# headphone.net
KiCad netlist of a schematic drawn in EAGLE
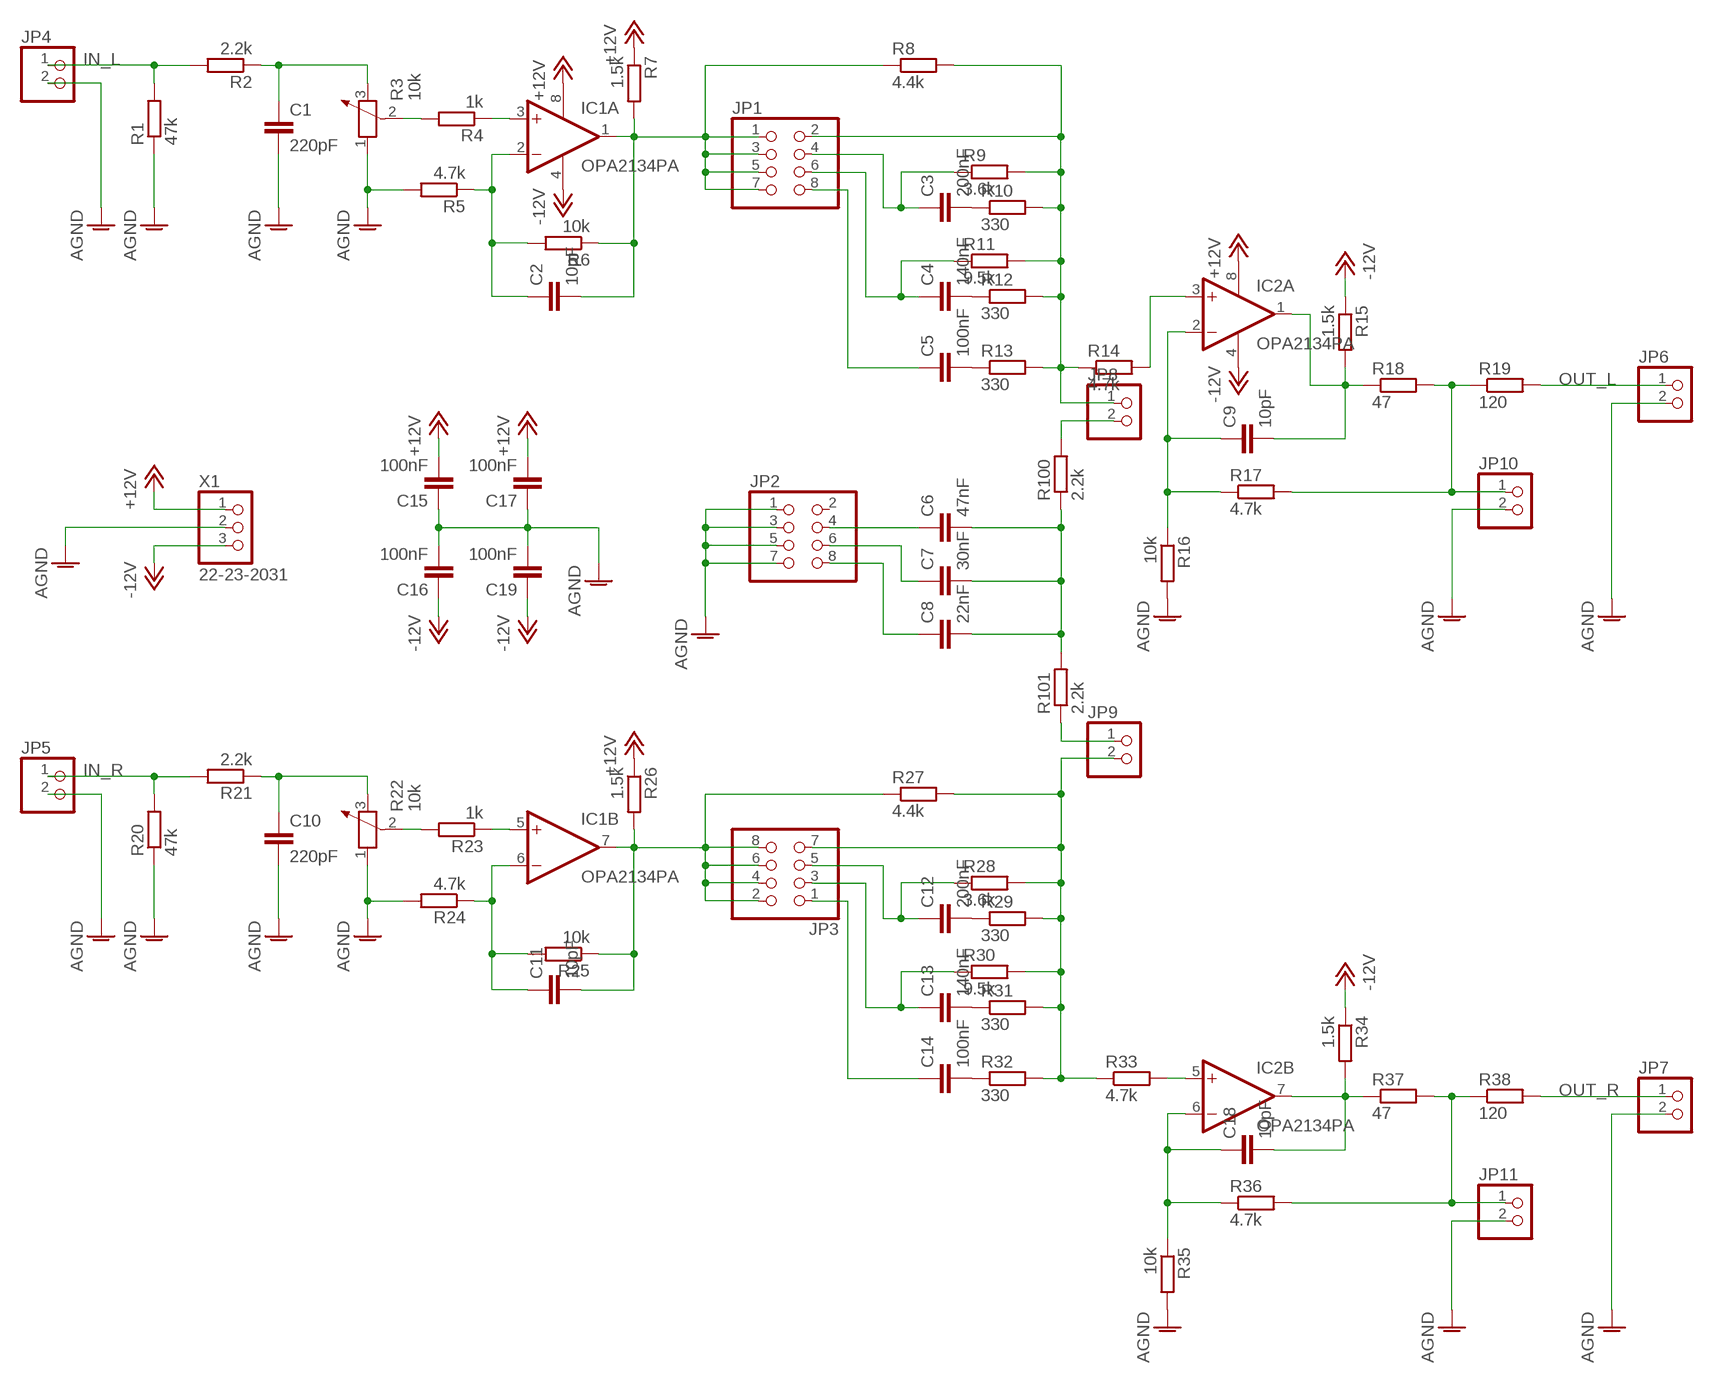
[diagram p0: schematic, sheet 1]

(export (version "E")
  (design (tool "Eeschema 10.0.6"))
  (components
    (comp (ref "C1")
      (value "220pF")
      (footprint "eagle-import:C025-025X050")
      (libsource (lib "eagle-import") (part "C-EU025-025X050"))
    )
    (comp (ref "C2")
      (value "10pF")
      (footprint "eagle-import:C050-025X075")
      (libsource (lib "eagle-import") (part "C-EU050-025X075"))
    )
    (comp (ref "C3")
      (value "200nF")
      (footprint "eagle-import:C050-025X075")
      (libsource (lib "eagle-import") (part "C-EU050-025X075"))
    )
    (comp (ref "C4")
      (value "140nF")
      (footprint "eagle-import:C050-025X075")
      (libsource (lib "eagle-import") (part "C-EU050-025X075"))
    )
    (comp (ref "C5")
      (value "100nF")
      (footprint "eagle-import:C050-025X075")
      (libsource (lib "eagle-import") (part "C-EU050-025X075"))
    )
    (comp (ref "C6")
      (value "47nF")
      (footprint "eagle-import:C050-025X075")
      (libsource (lib "eagle-import") (part "C-EU050-025X075"))
    )
    (comp (ref "C7")
      (value "30nF")
      (footprint "eagle-import:C050-025X075")
      (libsource (lib "eagle-import") (part "C-EU050-025X075"))
    )
    (comp (ref "C8")
      (value "22nF")
      (footprint "eagle-import:C050-025X075")
      (libsource (lib "eagle-import") (part "C-EU050-025X075"))
    )
    (comp (ref "C9")
      (value "10pF")
      (footprint "eagle-import:C050-025X075")
      (libsource (lib "eagle-import") (part "C-EU050-025X075"))
    )
    (comp (ref "C10")
      (value "220pF")
      (footprint "eagle-import:C025-025X050")
      (libsource (lib "eagle-import") (part "C-EU025-025X050"))
    )
    (comp (ref "C11")
      (value "10pF")
      (footprint "eagle-import:C050-025X075")
      (libsource (lib "eagle-import") (part "C-EU050-025X075"))
    )
    (comp (ref "C12")
      (value "200nF")
      (footprint "eagle-import:C050-025X075")
      (libsource (lib "eagle-import") (part "C-EU050-025X075"))
    )
    (comp (ref "C13")
      (value "140nF")
      (footprint "eagle-import:C050-025X075")
      (libsource (lib "eagle-import") (part "C-EU050-025X075"))
    )
    (comp (ref "C14")
      (value "100nF")
      (footprint "eagle-import:C050-025X075")
      (libsource (lib "eagle-import") (part "C-EU050-025X075"))
    )
    (comp (ref "C15")
      (value "100nF")
      (footprint "eagle-import:C050-025X075")
      (libsource (lib "eagle-import") (part "C-EU050-025X075"))
    )
    (comp (ref "C16")
      (value "100nF")
      (footprint "eagle-import:C050-025X075")
      (libsource (lib "eagle-import") (part "C-EU050-025X075"))
    )
    (comp (ref "C17")
      (value "100nF")
      (footprint "eagle-import:C050-025X075")
      (libsource (lib "eagle-import") (part "C-EU050-025X075"))
    )
    (comp (ref "C18")
      (value "10pF")
      (footprint "eagle-import:C050-025X075")
      (libsource (lib "eagle-import") (part "C-EU050-025X075"))
    )
    (comp (ref "C19")
      (value "100nF")
      (footprint "eagle-import:C050-025X075")
      (libsource (lib "eagle-import") (part "C-EU050-025X075"))
    )
    (comp (ref "IC1")
      (value "OPA2134PA")
      (footprint "eagle-import:DIL08")
      (libsource (lib "eagle-import") (part "OPA2PA134"))
    )
    (comp (ref "IC2")
      (value "OPA2134PA")
      (footprint "eagle-import:DIL08")
      (libsource (lib "eagle-import") (part "OPA2PA134"))
    )
    (comp (ref "JP1")
      (value "PINHD-2X4")
      (footprint "eagle-import:2X04")
      (libsource (lib "eagle-import") (part "PINHD-2X4"))
    )
    (comp (ref "JP2")
      (value "PINHD-2X4")
      (footprint "eagle-import:2X04")
      (libsource (lib "eagle-import") (part "PINHD-2X4"))
    )
    (comp (ref "JP3")
      (value "PINHD-2X4")
      (footprint "eagle-import:2X04")
      (libsource (lib "eagle-import") (part "PINHD-2X4"))
    )
    (comp (ref "JP4")
      (value "PINHD-1X2")
      (footprint "eagle-import:1X02")
      (libsource (lib "eagle-import") (part "PINHD-1X2"))
    )
    (comp (ref "JP5")
      (value "PINHD-1X2")
      (footprint "eagle-import:1X02")
      (libsource (lib "eagle-import") (part "PINHD-1X2"))
    )
    (comp (ref "JP6")
      (value "PINHD-1X2")
      (footprint "eagle-import:1X02")
      (libsource (lib "eagle-import") (part "PINHD-1X2"))
    )
    (comp (ref "JP7")
      (value "PINHD-1X2")
      (footprint "eagle-import:1X02")
      (libsource (lib "eagle-import") (part "PINHD-1X2"))
    )
    (comp (ref "JP8")
      (value "PINHD-1X2")
      (footprint "eagle-import:1X02")
      (libsource (lib "eagle-import") (part "PINHD-1X2"))
    )
    (comp (ref "JP9")
      (value "PINHD-1X2")
      (footprint "eagle-import:1X02")
      (libsource (lib "eagle-import") (part "PINHD-1X2"))
    )
    (comp (ref "JP10")
      (value "PINHD-1X2")
      (footprint "eagle-import:1X02")
      (libsource (lib "eagle-import") (part "PINHD-1X2"))
    )
    (comp (ref "JP11")
      (value "PINHD-1X2")
      (footprint "eagle-import:1X02")
      (libsource (lib "eagle-import") (part "PINHD-1X2"))
    )
    (comp (ref "R1")
      (value "47k")
      (footprint "eagle-import:0207_7")
      (libsource (lib "eagle-import") (part "R-EU_0207/7"))
    )
    (comp (ref "R2")
      (value "2.2k")
      (footprint "eagle-import:0207_7")
      (libsource (lib "eagle-import") (part "R-EU_0207/7"))
    )
    (comp (ref "R3")
      (value "10k")
      (footprint "eagle-import:1X03")
      (libsource (lib "eagle-import") (part "POTENTIOMETER_"))
    )
    (comp (ref "R4")
      (value "1k")
      (footprint "eagle-import:0207_7")
      (libsource (lib "eagle-import") (part "R-EU_0207/7"))
    )
    (comp (ref "R5")
      (value "4.7k")
      (footprint "eagle-import:0207_7")
      (libsource (lib "eagle-import") (part "R-EU_0207/7"))
    )
    (comp (ref "R6")
      (value "10k")
      (footprint "eagle-import:0207_7")
      (libsource (lib "eagle-import") (part "R-EU_0207/7"))
    )
    (comp (ref "R7")
      (value "1.5k")
      (footprint "eagle-import:0207_7")
      (libsource (lib "eagle-import") (part "R-EU_0207/7"))
    )
    (comp (ref "R8")
      (value "4.4k")
      (footprint "eagle-import:0207_7")
      (libsource (lib "eagle-import") (part "R-EU_0207/7"))
    )
    (comp (ref "R9")
      (value "3.6k")
      (footprint "eagle-import:0207_7")
      (libsource (lib "eagle-import") (part "R-EU_0207/7"))
    )
    (comp (ref "R10")
      (value "330")
      (footprint "eagle-import:0207_7")
      (libsource (lib "eagle-import") (part "R-EU_0207/7"))
    )
    (comp (ref "R11")
      (value "9.5k")
      (footprint "eagle-import:0207_7")
      (libsource (lib "eagle-import") (part "R-EU_0207/7"))
    )
    (comp (ref "R12")
      (value "330")
      (footprint "eagle-import:0207_7")
      (libsource (lib "eagle-import") (part "R-EU_0207/7"))
    )
    (comp (ref "R13")
      (value "330")
      (footprint "eagle-import:0207_7")
      (libsource (lib "eagle-import") (part "R-EU_0207/7"))
    )
    (comp (ref "R14")
      (value "4.7k")
      (footprint "eagle-import:0207_7")
      (libsource (lib "eagle-import") (part "R-EU_0207/7"))
    )
    (comp (ref "R15")
      (value "1.5k")
      (footprint "eagle-import:0207_7")
      (libsource (lib "eagle-import") (part "R-EU_0207/7"))
    )
    (comp (ref "R16")
      (value "10k")
      (footprint "eagle-import:0207_7")
      (libsource (lib "eagle-import") (part "R-EU_0207/7"))
    )
    (comp (ref "R17")
      (value "4.7k")
      (footprint "eagle-import:0207_7")
      (libsource (lib "eagle-import") (part "R-EU_0207/7"))
    )
    (comp (ref "R18")
      (value "47")
      (footprint "eagle-import:0207_7")
      (libsource (lib "eagle-import") (part "R-EU_0207/7"))
    )
    (comp (ref "R19")
      (value "120")
      (footprint "eagle-import:0207_7")
      (libsource (lib "eagle-import") (part "R-EU_0207/7"))
    )
    (comp (ref "R20")
      (value "47k")
      (footprint "eagle-import:0207_7")
      (libsource (lib "eagle-import") (part "R-EU_0207/7"))
    )
    (comp (ref "R21")
      (value "2.2k")
      (footprint "eagle-import:0207_7")
      (libsource (lib "eagle-import") (part "R-EU_0207/7"))
    )
    (comp (ref "R22")
      (value "10k")
      (footprint "eagle-import:1X03")
      (libsource (lib "eagle-import") (part "POTENTIOMETER_"))
    )
    (comp (ref "R23")
      (value "1k")
      (footprint "eagle-import:0207_7")
      (libsource (lib "eagle-import") (part "R-EU_0207/7"))
    )
    (comp (ref "R24")
      (value "4.7k")
      (footprint "eagle-import:0207_7")
      (libsource (lib "eagle-import") (part "R-EU_0207/7"))
    )
    (comp (ref "R25")
      (value "10k")
      (footprint "eagle-import:0207_7")
      (libsource (lib "eagle-import") (part "R-EU_0207/7"))
    )
    (comp (ref "R26")
      (value "1.5k")
      (footprint "eagle-import:0207_7")
      (libsource (lib "eagle-import") (part "R-EU_0207/7"))
    )
    (comp (ref "R27")
      (value "4.4k")
      (footprint "eagle-import:0207_7")
      (libsource (lib "eagle-import") (part "R-EU_0207/7"))
    )
    (comp (ref "R28")
      (value "3.6k")
      (footprint "eagle-import:0207_7")
      (libsource (lib "eagle-import") (part "R-EU_0207/7"))
    )
    (comp (ref "R29")
      (value "330")
      (footprint "eagle-import:0207_7")
      (libsource (lib "eagle-import") (part "R-EU_0207/7"))
    )
    (comp (ref "R30")
      (value "9.5k")
      (footprint "eagle-import:0207_7")
      (libsource (lib "eagle-import") (part "R-EU_0207/7"))
    )
    (comp (ref "R31")
      (value "330")
      (footprint "eagle-import:0207_7")
      (libsource (lib "eagle-import") (part "R-EU_0207/7"))
    )
    (comp (ref "R32")
      (value "330")
      (footprint "eagle-import:0207_7")
      (libsource (lib "eagle-import") (part "R-EU_0207/7"))
    )
    (comp (ref "R33")
      (value "4.7k")
      (footprint "eagle-import:0207_7")
      (libsource (lib "eagle-import") (part "R-EU_0207/7"))
    )
    (comp (ref "R34")
      (value "1.5k")
      (footprint "eagle-import:0207_7")
      (libsource (lib "eagle-import") (part "R-EU_0207/7"))
    )
    (comp (ref "R35")
      (value "10k")
      (footprint "eagle-import:0207_7")
      (libsource (lib "eagle-import") (part "R-EU_0207/7"))
    )
    (comp (ref "R36")
      (value "4.7k")
      (footprint "eagle-import:0207_7")
      (libsource (lib "eagle-import") (part "R-EU_0207/7"))
    )
    (comp (ref "R37")
      (value "47")
      (footprint "eagle-import:0207_7")
      (libsource (lib "eagle-import") (part "R-EU_0207/7"))
    )
    (comp (ref "R38")
      (value "120")
      (footprint "eagle-import:0207_7")
      (libsource (lib "eagle-import") (part "R-EU_0207/7"))
    )
    (comp (ref "R100")
      (value "2.2k")
      (footprint "eagle-import:0207_7")
      (libsource (lib "eagle-import") (part "R-EU_0207/7"))
    )
    (comp (ref "R101")
      (value "2.2k")
      (footprint "eagle-import:0207_7")
      (libsource (lib "eagle-import") (part "R-EU_0207/7"))
    )
    (comp (ref "X1")
      (value "22-23-2031")
      (footprint "eagle-import:22-23-2031")
      (libsource (lib "eagle-import") (part "22-23-2031"))
    )
  )
  (nets
    (net (code "1") (name "+12V") (class "Default")
      (node (ref "C15") (pin "2") (pinfunction "2_2") (pintype "passive"))
      (node (ref "C17") (pin "2") (pinfunction "2_2") (pintype "passive"))
      (node (ref "IC1") (pin "8") (pinfunction "V+_8") (pintype "power_in"))
      (node (ref "IC2") (pin "8") (pinfunction "V+_8") (pintype "power_in"))
      (node (ref "R26") (pin "1") (pinfunction "1_1") (pintype "passive"))
      (node (ref "R7") (pin "1") (pinfunction "1_1") (pintype "passive"))
      (node (ref "X1") (pin "1") (pinfunction "1_1") (pintype "passive"))
    )
    (net (code "2") (name "-12V") (class "Default")
      (node (ref "C16") (pin "1") (pinfunction "1_1") (pintype "passive"))
      (node (ref "C19") (pin "1") (pinfunction "1_1") (pintype "passive"))
      (node (ref "IC1") (pin "4") (pinfunction "V-_4") (pintype "power_in"))
      (node (ref "IC2") (pin "4") (pinfunction "V-_4") (pintype "power_in"))
      (node (ref "R15") (pin "1") (pinfunction "1_1") (pintype "passive"))
      (node (ref "R34") (pin "1") (pinfunction "1_1") (pintype "passive"))
      (node (ref "X1") (pin "3") (pinfunction "3_3") (pintype "passive"))
    )
    (net (code "3") (name "/IN_L") (class "Default")
      (node (ref "JP4") (pin "1") (pinfunction "1_1") (pintype "passive"))
      (node (ref "R1") (pin "2") (pinfunction "2_2") (pintype "passive"))
      (node (ref "R2") (pin "2") (pinfunction "2_2") (pintype "passive"))
    )
    (net (code "4") (name "/IN_R") (class "Default")
      (node (ref "JP5") (pin "1") (pinfunction "1_1") (pintype "passive"))
      (node (ref "R20") (pin "2") (pinfunction "2_2") (pintype "passive"))
      (node (ref "R21") (pin "2") (pinfunction "2_2") (pintype "passive"))
    )
    (net (code "5") (name "/OUT_L") (class "Default")
      (node (ref "JP6") (pin "1") (pinfunction "1_1") (pintype "passive"))
      (node (ref "R19") (pin "2") (pinfunction "2_2") (pintype "passive"))
    )
    (net (code "6") (name "/OUT_R") (class "Default")
      (node (ref "JP7") (pin "1") (pinfunction "1_1") (pintype "passive"))
      (node (ref "R38") (pin "2") (pinfunction "2_2") (pintype "passive"))
    )
    (net (code "7") (name "AGND") (class "Default")
      (node (ref "C1") (pin "2") (pinfunction "2_2") (pintype "passive"))
      (node (ref "C10") (pin "2") (pinfunction "2_2") (pintype "passive"))
      (node (ref "C15") (pin "1") (pinfunction "1_1") (pintype "passive"))
      (node (ref "C16") (pin "2") (pinfunction "2_2") (pintype "passive"))
      (node (ref "C17") (pin "1") (pinfunction "1_1") (pintype "passive"))
      (node (ref "C19") (pin "2") (pinfunction "2_2") (pintype "passive"))
      (node (ref "JP10") (pin "2") (pinfunction "2_2") (pintype "passive"))
      (node (ref "JP11") (pin "2") (pinfunction "2_2") (pintype "passive"))
      (node (ref "JP2") (pin "1") (pinfunction "1_1") (pintype "passive"))
      (node (ref "JP2") (pin "3") (pinfunction "3_3") (pintype "passive"))
      (node (ref "JP2") (pin "5") (pinfunction "5_5") (pintype "passive"))
      (node (ref "JP2") (pin "7") (pinfunction "7_7") (pintype "passive"))
      (node (ref "JP4") (pin "2") (pinfunction "2_2") (pintype "passive"))
      (node (ref "JP5") (pin "2") (pinfunction "2_2") (pintype "passive"))
      (node (ref "JP6") (pin "2") (pinfunction "2_2") (pintype "passive"))
      (node (ref "JP7") (pin "2") (pinfunction "2_2") (pintype "passive"))
      (node (ref "R1") (pin "1") (pinfunction "1_1") (pintype "passive"))
      (node (ref "R16") (pin "2") (pinfunction "2_2") (pintype "passive"))
      (node (ref "R20") (pin "1") (pinfunction "1_1") (pintype "passive"))
      (node (ref "R22") (pin "1") (pinfunction "1_1") (pintype "passive"))
      (node (ref "R24") (pin "2") (pinfunction "2_2") (pintype "passive"))
      (node (ref "R3") (pin "1") (pinfunction "1_1") (pintype "passive"))
      (node (ref "R35") (pin "2") (pinfunction "2_2") (pintype "passive"))
      (node (ref "R5") (pin "2") (pinfunction "2_2") (pintype "passive"))
      (node (ref "X1") (pin "2") (pinfunction "2_2") (pintype "passive"))
    )
    (net (code "8") (name "Net-(C3-Pad1)") (class "Default")
      (node (ref "C3") (pin "1") (pinfunction "1_1") (pintype "passive"))
      (node (ref "JP1") (pin "4") (pinfunction "4_4") (pintype "passive"))
      (node (ref "R9") (pin "1") (pinfunction "1_1") (pintype "passive"))
    )
    (net (code "9") (name "Net-(C3-Pad2)") (class "Default")
      (node (ref "C3") (pin "2") (pinfunction "2_2") (pintype "passive"))
      (node (ref "R10") (pin "1") (pinfunction "1_1") (pintype "passive"))
    )
    (net (code "10") (name "Net-(C4-Pad1)") (class "Default")
      (node (ref "C4") (pin "1") (pinfunction "1_1") (pintype "passive"))
      (node (ref "JP1") (pin "6") (pinfunction "6_6") (pintype "passive"))
      (node (ref "R11") (pin "1") (pinfunction "1_1") (pintype "passive"))
    )
    (net (code "11") (name "Net-(C4-Pad2)") (class "Default")
      (node (ref "C4") (pin "2") (pinfunction "2_2") (pintype "passive"))
      (node (ref "R12") (pin "1") (pinfunction "1_1") (pintype "passive"))
    )
    (net (code "12") (name "Net-(C5-Pad1)") (class "Default")
      (node (ref "C5") (pin "1") (pinfunction "1_1") (pintype "passive"))
      (node (ref "JP1") (pin "8") (pinfunction "8_8") (pintype "passive"))
    )
    (net (code "13") (name "Net-(C5-Pad2)") (class "Default")
      (node (ref "C5") (pin "2") (pinfunction "2_2") (pintype "passive"))
      (node (ref "R13") (pin "1") (pinfunction "1_1") (pintype "passive"))
    )
    (net (code "14") (name "Net-(C6-Pad1)") (class "Default")
      (node (ref "C6") (pin "1") (pinfunction "1_1") (pintype "passive"))
      (node (ref "JP2") (pin "4") (pinfunction "4_4") (pintype "passive"))
    )
    (net (code "15") (name "Net-(C6-Pad2)") (class "Default")
      (node (ref "C6") (pin "2") (pinfunction "2_2") (pintype "passive"))
      (node (ref "C7") (pin "2") (pinfunction "2_2") (pintype "passive"))
      (node (ref "C8") (pin "2") (pinfunction "2_2") (pintype "passive"))
      (node (ref "R100") (pin "1") (pinfunction "1_1") (pintype "passive"))
      (node (ref "R101") (pin "2") (pinfunction "2_2") (pintype "passive"))
    )
    (net (code "16") (name "Net-(C7-Pad1)") (class "Default")
      (node (ref "C7") (pin "1") (pinfunction "1_1") (pintype "passive"))
      (node (ref "JP2") (pin "6") (pinfunction "6_6") (pintype "passive"))
    )
    (net (code "17") (name "Net-(C8-Pad1)") (class "Default")
      (node (ref "C8") (pin "1") (pinfunction "1_1") (pintype "passive"))
      (node (ref "JP2") (pin "8") (pinfunction "8_8") (pintype "passive"))
    )
    (net (code "18") (name "Net-(C12-Pad1)") (class "Default")
      (node (ref "C12") (pin "1") (pinfunction "1_1") (pintype "passive"))
      (node (ref "JP3") (pin "5") (pinfunction "5_5") (pintype "passive"))
      (node (ref "R28") (pin "1") (pinfunction "1_1") (pintype "passive"))
    )
    (net (code "19") (name "Net-(C12-Pad2)") (class "Default")
      (node (ref "C12") (pin "2") (pinfunction "2_2") (pintype "passive"))
      (node (ref "R29") (pin "1") (pinfunction "1_1") (pintype "passive"))
    )
    (net (code "20") (name "Net-(C13-Pad1)") (class "Default")
      (node (ref "C13") (pin "1") (pinfunction "1_1") (pintype "passive"))
      (node (ref "JP3") (pin "3") (pinfunction "3_3") (pintype "passive"))
      (node (ref "R30") (pin "1") (pinfunction "1_1") (pintype "passive"))
    )
    (net (code "21") (name "Net-(C13-Pad2)") (class "Default")
      (node (ref "C13") (pin "2") (pinfunction "2_2") (pintype "passive"))
      (node (ref "R31") (pin "1") (pinfunction "1_1") (pintype "passive"))
    )
    (net (code "22") (name "Net-(C14-Pad1)") (class "Default")
      (node (ref "C14") (pin "1") (pinfunction "1_1") (pintype "passive"))
      (node (ref "JP3") (pin "1") (pinfunction "1_1") (pintype "passive"))
    )
    (net (code "23") (name "Net-(C14-Pad2)") (class "Default")
      (node (ref "C14") (pin "2") (pinfunction "2_2") (pintype "passive"))
      (node (ref "R32") (pin "1") (pinfunction "1_1") (pintype "passive"))
    )
    (net (code "24") (name "Net-(IC1A-+IN)") (class "Default")
      (node (ref "IC1") (pin "3") (pinfunction "+IN_3") (pintype "input"))
      (node (ref "R4") (pin "1") (pinfunction "1_1") (pintype "passive"))
    )
    (net (code "25") (name "Net-(IC1A--IN)") (class "Default")
      (node (ref "C2") (pin "1") (pinfunction "1_1") (pintype "passive"))
      (node (ref "IC1") (pin "2") (pinfunction "-IN_2") (pintype "input"))
      (node (ref "R5") (pin "1") (pinfunction "1_1") (pintype "passive"))
      (node (ref "R6") (pin "2") (pinfunction "2_2") (pintype "passive"))
    )
    (net (code "26") (name "Net-(IC1A-OUT)") (class "Default")
      (node (ref "C2") (pin "2") (pinfunction "2_2") (pintype "passive"))
      (node (ref "IC1") (pin "1") (pinfunction "OUT_1") (pintype "output"))
      (node (ref "JP1") (pin "1") (pinfunction "1_1") (pintype "passive"))
      (node (ref "JP1") (pin "3") (pinfunction "3_3") (pintype "passive"))
      (node (ref "JP1") (pin "5") (pinfunction "5_5") (pintype "passive"))
      (node (ref "JP1") (pin "7") (pinfunction "7_7") (pintype "passive"))
      (node (ref "R6") (pin "1") (pinfunction "1_1") (pintype "passive"))
      (node (ref "R7") (pin "2") (pinfunction "2_2") (pintype "passive"))
      (node (ref "R8") (pin "1") (pinfunction "1_1") (pintype "passive"))
    )
    (net (code "27") (name "Net-(IC1B-+IN)") (class "Default")
      (node (ref "IC1") (pin "5") (pinfunction "+IN_5") (pintype "input"))
      (node (ref "R23") (pin "1") (pinfunction "1_1") (pintype "passive"))
    )
    (net (code "28") (name "Net-(IC1B--IN)") (class "Default")
      (node (ref "C11") (pin "1") (pinfunction "1_1") (pintype "passive"))
      (node (ref "IC1") (pin "6") (pinfunction "-IN_6") (pintype "input"))
      (node (ref "R24") (pin "1") (pinfunction "1_1") (pintype "passive"))
      (node (ref "R25") (pin "2") (pinfunction "2_2") (pintype "passive"))
    )
    (net (code "29") (name "Net-(IC1B-OUT)") (class "Default")
      (node (ref "C11") (pin "2") (pinfunction "2_2") (pintype "passive"))
      (node (ref "IC1") (pin "7") (pinfunction "OUT_7") (pintype "output"))
      (node (ref "JP3") (pin "2") (pinfunction "2_2") (pintype "passive"))
      (node (ref "JP3") (pin "4") (pinfunction "4_4") (pintype "passive"))
      (node (ref "JP3") (pin "6") (pinfunction "6_6") (pintype "passive"))
      (node (ref "JP3") (pin "8") (pinfunction "8_8") (pintype "passive"))
      (node (ref "R25") (pin "1") (pinfunction "1_1") (pintype "passive"))
      (node (ref "R26") (pin "2") (pinfunction "2_2") (pintype "passive"))
      (node (ref "R27") (pin "1") (pinfunction "1_1") (pintype "passive"))
    )
    (net (code "30") (name "Net-(IC2A-+IN)") (class "Default")
      (node (ref "IC2") (pin "3") (pinfunction "+IN_3") (pintype "input"))
      (node (ref "R14") (pin "2") (pinfunction "2_2") (pintype "passive"))
    )
    (net (code "31") (name "Net-(IC2A--IN)") (class "Default")
      (node (ref "C9") (pin "1") (pinfunction "1_1") (pintype "passive"))
      (node (ref "IC2") (pin "2") (pinfunction "-IN_2") (pintype "input"))
      (node (ref "R16") (pin "1") (pinfunction "1_1") (pintype "passive"))
      (node (ref "R17") (pin "1") (pinfunction "1_1") (pintype "passive"))
    )
    (net (code "32") (name "Net-(IC2A-OUT)") (class "Default")
      (node (ref "C9") (pin "2") (pinfunction "2_2") (pintype "passive"))
      (node (ref "IC2") (pin "1") (pinfunction "OUT_1") (pintype "output"))
      (node (ref "R15") (pin "2") (pinfunction "2_2") (pintype "passive"))
      (node (ref "R18") (pin "1") (pinfunction "1_1") (pintype "passive"))
    )
    (net (code "33") (name "Net-(IC2B-+IN)") (class "Default")
      (node (ref "IC2") (pin "5") (pinfunction "+IN_5") (pintype "input"))
      (node (ref "R33") (pin "2") (pinfunction "2_2") (pintype "passive"))
    )
    (net (code "34") (name "Net-(IC2B--IN)") (class "Default")
      (node (ref "C18") (pin "1") (pinfunction "1_1") (pintype "passive"))
      (node (ref "IC2") (pin "6") (pinfunction "-IN_6") (pintype "input"))
      (node (ref "R35") (pin "1") (pinfunction "1_1") (pintype "passive"))
      (node (ref "R36") (pin "1") (pinfunction "1_1") (pintype "passive"))
    )
    (net (code "35") (name "Net-(IC2B-OUT)") (class "Default")
      (node (ref "C18") (pin "2") (pinfunction "2_2") (pintype "passive"))
      (node (ref "IC2") (pin "7") (pinfunction "OUT_7") (pintype "output"))
      (node (ref "R34") (pin "2") (pinfunction "2_2") (pintype "passive"))
      (node (ref "R37") (pin "1") (pinfunction "1_1") (pintype "passive"))
    )
    (net (code "36") (name "Net-(JP1-Pad2)") (class "Default")
      (node (ref "JP1") (pin "2") (pinfunction "2_2") (pintype "passive"))
      (node (ref "JP8") (pin "1") (pinfunction "1_1") (pintype "passive"))
      (node (ref "R10") (pin "2") (pinfunction "2_2") (pintype "passive"))
      (node (ref "R11") (pin "2") (pinfunction "2_2") (pintype "passive"))
      (node (ref "R12") (pin "2") (pinfunction "2_2") (pintype "passive"))
      (node (ref "R13") (pin "2") (pinfunction "2_2") (pintype "passive"))
      (node (ref "R14") (pin "1") (pinfunction "1_1") (pintype "passive"))
      (node (ref "R8") (pin "2") (pinfunction "2_2") (pintype "passive"))
      (node (ref "R9") (pin "2") (pinfunction "2_2") (pintype "passive"))
    )
    (net (code "37") (name "Net-(JP3-Pad7)") (class "Default")
      (node (ref "JP3") (pin "7") (pinfunction "7_7") (pintype "passive"))
      (node (ref "JP9") (pin "2") (pinfunction "2_2") (pintype "passive"))
      (node (ref "R27") (pin "2") (pinfunction "2_2") (pintype "passive"))
      (node (ref "R28") (pin "2") (pinfunction "2_2") (pintype "passive"))
      (node (ref "R29") (pin "2") (pinfunction "2_2") (pintype "passive"))
      (node (ref "R30") (pin "2") (pinfunction "2_2") (pintype "passive"))
      (node (ref "R31") (pin "2") (pinfunction "2_2") (pintype "passive"))
      (node (ref "R32") (pin "2") (pinfunction "2_2") (pintype "passive"))
      (node (ref "R33") (pin "1") (pinfunction "1_1") (pintype "passive"))
    )
    (net (code "38") (name "Net-(JP8-Pad2)") (class "Default")
      (node (ref "JP8") (pin "2") (pinfunction "2_2") (pintype "passive"))
      (node (ref "R100") (pin "2") (pinfunction "2_2") (pintype "passive"))
    )
    (net (code "39") (name "Net-(JP9-Pad1)") (class "Default")
      (node (ref "JP9") (pin "1") (pinfunction "1_1") (pintype "passive"))
      (node (ref "R101") (pin "1") (pinfunction "1_1") (pintype "passive"))
    )
    (net (code "40") (name "Net-(JP10-Pad1)") (class "Default")
      (node (ref "JP10") (pin "1") (pinfunction "1_1") (pintype "passive"))
      (node (ref "R17") (pin "2") (pinfunction "2_2") (pintype "passive"))
      (node (ref "R18") (pin "2") (pinfunction "2_2") (pintype "passive"))
      (node (ref "R19") (pin "1") (pinfunction "1_1") (pintype "passive"))
    )
    (net (code "41") (name "Net-(JP11-Pad1)") (class "Default")
      (node (ref "JP11") (pin "1") (pinfunction "1_1") (pintype "passive"))
      (node (ref "R36") (pin "2") (pinfunction "2_2") (pintype "passive"))
      (node (ref "R37") (pin "2") (pinfunction "2_2") (pintype "passive"))
      (node (ref "R38") (pin "1") (pinfunction "1_1") (pintype "passive"))
    )
    (net (code "42") (name "Net-(R3-2)") (class "Default")
      (node (ref "C1") (pin "1") (pinfunction "1_1") (pintype "passive"))
      (node (ref "R2") (pin "1") (pinfunction "1_1") (pintype "passive"))
      (node (ref "R3") (pin "3") (pinfunction "2_3") (pintype "passive"))
    )
    (net (code "43") (name "Net-(R3-3)") (class "Default")
      (node (ref "R3") (pin "2") (pinfunction "3_2") (pintype "passive"))
      (node (ref "R4") (pin "2") (pinfunction "2_2") (pintype "passive"))
    )
    (net (code "44") (name "Net-(R22-2)") (class "Default")
      (node (ref "C10") (pin "1") (pinfunction "1_1") (pintype "passive"))
      (node (ref "R21") (pin "1") (pinfunction "1_1") (pintype "passive"))
      (node (ref "R22") (pin "3") (pinfunction "2_3") (pintype "passive"))
    )
    (net (code "45") (name "Net-(R22-3)") (class "Default")
      (node (ref "R22") (pin "2") (pinfunction "3_2") (pintype "passive"))
      (node (ref "R23") (pin "2") (pinfunction "2_2") (pintype "passive"))
    )
    (net (code "46") (name "unconnected-(JP2-Pad2)") (class "Default")
      (node (ref "JP2") (pin "2") (pinfunction "2_2") (pintype "passive"))
    )
  )
)
